# blinkercough.net
KiCad netlist of a schematic drawn in EAGLE
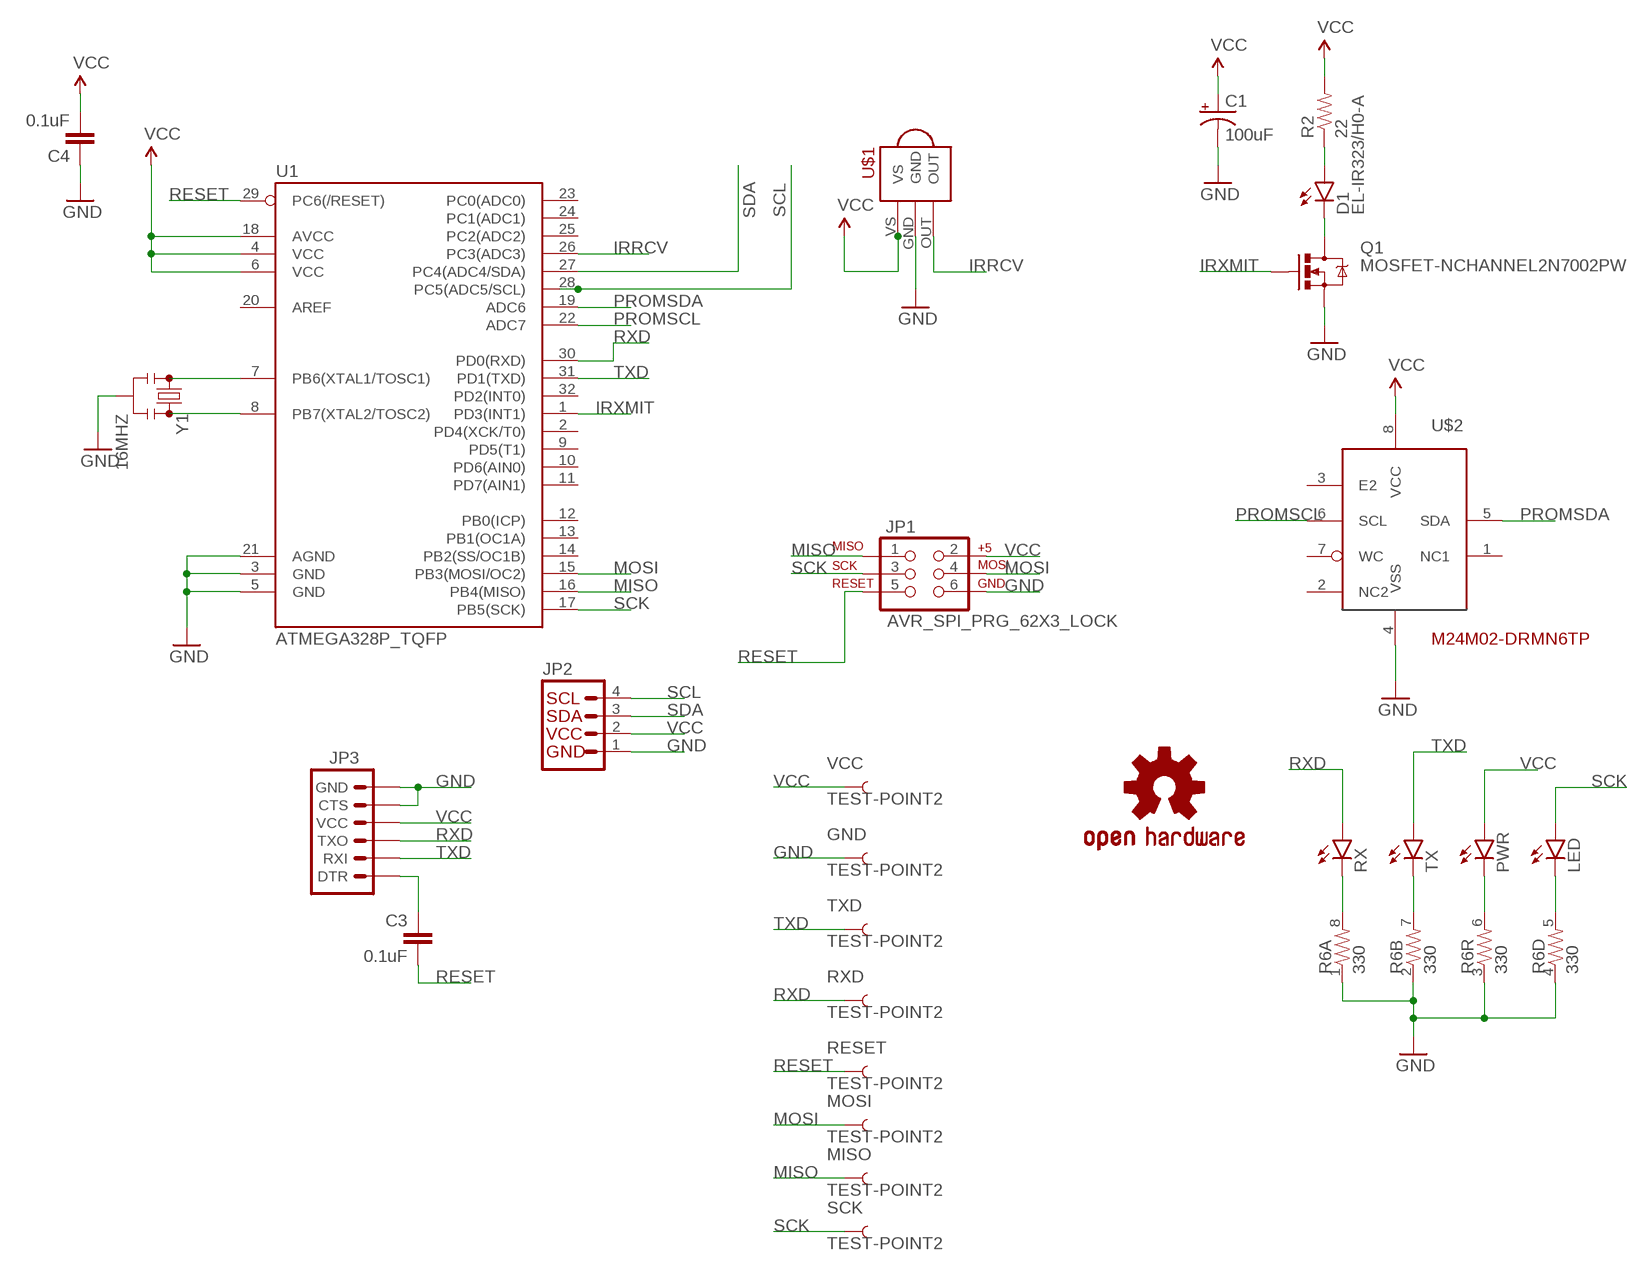
[diagram p0: schematic, sheet 1]

(export (version "E")
  (design (tool "Eeschema 10.0.6"))
  (components
    (comp (ref "C1")
      (value "100uF")
      (footprint "eagle-import:EIA7343")
      (libsource (lib "eagle-import") (part "100UF-10V-10%(TANT)"))
    )
    (comp (ref "C3")
      (value "0.1uF")
      (footprint "eagle-import:0603-CAP")
      (libsource (lib "eagle-import") (part "0.1UF-25V(+80/-20%)(0603)"))
    )
    (comp (ref "C4")
      (value "0.1uF")
      (footprint "eagle-import:0603-CAP")
      (libsource (lib "eagle-import") (part "0.1UF-25V(+80/-20%)(0603)"))
    )
    (comp (ref "D1")
      (value "EL-IR323/H0-A")
      (footprint "eagle-import:LED3MM")
      (libsource (lib "eagle-import") (part "LED3MM"))
    )
    (comp (ref "GND")
      (value "TEST-POINT2")
      (footprint "eagle-import:PAD.02X.02")
      (libsource (lib "eagle-import") (part "TEST-POINT2"))
    )
    (comp (ref "JP1")
      (value "AVR_SPI_PRG_62X3_LOCK")
      (footprint "eagle-import:2X3_LOCK")
      (libsource (lib "eagle-import") (part "AVR_SPI_PRG_62X3_LOCK"))
    )
    (comp (ref "JP2")
      (value "I2C_STANDARD")
      (footprint "eagle-import:1X04")
      (libsource (lib "eagle-import") (part "I2C_STANDARD"))
    )
    (comp (ref "JP3")
      (value "ARDUINO_SERIAL_PROGRAMLOCK")
      (footprint "eagle-import:1X06_LOCK")
      (libsource (lib "eagle-import") (part "ARDUINO_SERIAL_PROGRAMLOCK"))
    )
    (comp (ref "LED")
      (value "LED0603")
      (footprint "eagle-import:LED-0603")
      (libsource (lib "eagle-import") (part "LED0603"))
    )
    (comp (ref "LOGO1")
      (value "OSHW-LOGOS")
      (footprint "eagle-import:OSHW-LOGO-S")
      (libsource (lib "eagle-import") (part "OSHW-LOGOS"))
    )
    (comp (ref "MISO")
      (value "TEST-POINT2")
      (footprint "eagle-import:PAD.02X.02")
      (libsource (lib "eagle-import") (part "TEST-POINT2"))
    )
    (comp (ref "MOSI")
      (value "TEST-POINT2")
      (footprint "eagle-import:PAD.02X.02")
      (libsource (lib "eagle-import") (part "TEST-POINT2"))
    )
    (comp (ref "PWR")
      (value "LED0603")
      (footprint "eagle-import:LED-0603")
      (libsource (lib "eagle-import") (part "LED0603"))
    )
    (comp (ref "Q1")
      (value "MOSFET-NCHANNEL2N7002PW")
      (footprint "eagle-import:SOT323")
      (libsource (lib "eagle-import") (part "MOSFET-NCHANNEL2N7002PW"))
    )
    (comp (ref "R2")
      (value "22")
      (footprint "eagle-import:1206")
      (libsource (lib "eagle-import") (part "RESISTOR1206"))
    )
    (comp (ref "R6")
      (value "330")
      (footprint "eagle-import:0603-ARV")
      (libsource (lib "eagle-import") (part "RESISTOR-ARRAY0603-ARV"))
    )
    (comp (ref "RESET")
      (value "TEST-POINT2")
      (footprint "eagle-import:PAD.02X.02")
      (libsource (lib "eagle-import") (part "TEST-POINT2"))
    )
    (comp (ref "RX")
      (value "LED0603")
      (footprint "eagle-import:LED-0603")
      (libsource (lib "eagle-import") (part "LED0603"))
    )
    (comp (ref "RXD")
      (value "TEST-POINT2")
      (footprint "eagle-import:PAD.02X.02")
      (libsource (lib "eagle-import") (part "TEST-POINT2"))
    )
    (comp (ref "SCK")
      (value "TEST-POINT2")
      (footprint "eagle-import:PAD.02X.02")
      (libsource (lib "eagle-import") (part "TEST-POINT2"))
    )
    (comp (ref "TX")
      (value "LED0603")
      (footprint "eagle-import:LED-0603")
      (libsource (lib "eagle-import") (part "LED0603"))
    )
    (comp (ref "TXD")
      (value "TEST-POINT2")
      (footprint "eagle-import:PAD.02X.02")
      (libsource (lib "eagle-import") (part "TEST-POINT2"))
    )
    (comp (ref "U$1")
      (value "TSOP2438")
      (footprint "eagle-import:TSOP2438")
      (libsource (lib "eagle-import") (part "TSOP2438"))
    )
    (comp (ref "U$2")
      (value "M24M02-DRMN6TP")
      (footprint "eagle-import:SO8")
      (libsource (lib "eagle-import") (part "M24M02-DRMN6TP"))
    )
    (comp (ref "U1")
      (value "ATMEGA328P_TQFP")
      (footprint "eagle-import:TQFP32-08")
      (libsource (lib "eagle-import") (part "ATMEGA328P_TQFP"))
    )
    (comp (ref "VCC")
      (value "TEST-POINT2")
      (footprint "eagle-import:PAD.02X.02")
      (libsource (lib "eagle-import") (part "TEST-POINT2"))
    )
    (comp (ref "Y1")
      (value "16MHZ")
      (footprint "eagle-import:RESONATOR-SMD")
      (libsource (lib "eagle-import") (part "RESONATOR16MHZ"))
    )
  )
  (nets
    (net (code "1") (name "/IRRCV") (class "Default")
      (node (ref "U$1") (pin "OUT") (pinfunction "OUT_OUT") (pintype "output"))
      (node (ref "U1") (pin "26") (pinfunction "PC3(ADC3)_26") (pintype "bidirectional"))
    )
    (net (code "2") (name "/IRXMIT") (class "Default")
      (node (ref "Q1") (pin "1") (pinfunction "G_1") (pintype "passive"))
      (node (ref "U1") (pin "1") (pinfunction "PD3(INT1)_1") (pintype "bidirectional"))
    )
    (net (code "3") (name "/MISO") (class "Default")
      (node (ref "JP1") (pin "1") (pinfunction "1_1") (pintype "passive"))
      (node (ref "MISO") (pin "P$1") (pinfunction "1_P$1") (pintype "bidirectional"))
      (node (ref "U1") (pin "16") (pinfunction "PB4(MISO)_16") (pintype "bidirectional"))
    )
    (net (code "4") (name "/MOSI") (class "Default")
      (node (ref "JP1") (pin "4") (pinfunction "4_4") (pintype "passive"))
      (node (ref "MOSI") (pin "P$1") (pinfunction "1_P$1") (pintype "bidirectional"))
      (node (ref "U1") (pin "15") (pinfunction "PB3(MOSI/OC2)_15") (pintype "bidirectional"))
    )
    (net (code "5") (name "/PROMSCL") (class "Default")
      (node (ref "U$2") (pin "6") (pinfunction "SCL_6") (pintype "bidirectional"))
      (node (ref "U1") (pin "22") (pinfunction "ADC7_22") (pintype "bidirectional"))
    )
    (net (code "6") (name "/PROMSDA") (class "Default")
      (node (ref "U$2") (pin "5") (pinfunction "SDA_5") (pintype "bidirectional"))
      (node (ref "U1") (pin "19") (pinfunction "ADC6_19") (pintype "bidirectional"))
    )
    (net (code "7") (name "/RESET") (class "Default")
      (node (ref "C3") (pin "2") (pinfunction "2_2") (pintype "passive"))
      (node (ref "JP1") (pin "5") (pinfunction "5_5") (pintype "passive"))
      (node (ref "RESET") (pin "P$1") (pinfunction "1_P$1") (pintype "bidirectional"))
      (node (ref "U1") (pin "29") (pinfunction "PC6(/RESET)_29") (pintype "bidirectional"))
    )
    (net (code "8") (name "/RXD") (class "Default")
      (node (ref "JP3") (pin "3") (pinfunction "TXO_3") (pintype "passive"))
      (node (ref "RX") (pin "A") (pinfunction "A_A") (pintype "passive"))
      (node (ref "RXD") (pin "P$1") (pinfunction "1_P$1") (pintype "bidirectional"))
      (node (ref "U1") (pin "30") (pinfunction "PD0(RXD)_30") (pintype "bidirectional"))
    )
    (net (code "9") (name "/SCK") (class "Default")
      (node (ref "JP1") (pin "3") (pinfunction "3_3") (pintype "passive"))
      (node (ref "LED") (pin "A") (pinfunction "A_A") (pintype "passive"))
      (node (ref "SCK") (pin "P$1") (pinfunction "1_P$1") (pintype "bidirectional"))
      (node (ref "U1") (pin "17") (pinfunction "PB5(SCK)_17") (pintype "bidirectional"))
    )
    (net (code "10") (name "/SCL") (class "Default")
      (node (ref "JP2") (pin "4") (pinfunction "4_4") (pintype "passive"))
      (node (ref "U1") (pin "28") (pinfunction "PC5(ADC5/SCL)_28") (pintype "bidirectional"))
    )
    (net (code "11") (name "/SDA") (class "Default")
      (node (ref "JP2") (pin "3") (pinfunction "3_3") (pintype "passive"))
      (node (ref "U1") (pin "27") (pinfunction "PC4(ADC4/SDA)_27") (pintype "bidirectional"))
    )
    (net (code "12") (name "/TXD") (class "Default")
      (node (ref "JP3") (pin "2") (pinfunction "RXI_2") (pintype "passive"))
      (node (ref "TX") (pin "A") (pinfunction "A_A") (pintype "passive"))
      (node (ref "TXD") (pin "P$1") (pinfunction "1_P$1") (pintype "bidirectional"))
      (node (ref "U1") (pin "31") (pinfunction "PD1(TXD)_31") (pintype "bidirectional"))
    )
    (net (code "13") (name "GND") (class "Default")
      (node (ref "C1") (pin "C") (pinfunction "-_C") (pintype "passive"))
      (node (ref "C4") (pin "1") (pinfunction "1_1") (pintype "passive"))
      (node (ref "GND") (pin "P$1") (pinfunction "1_P$1") (pintype "bidirectional"))
      (node (ref "JP1") (pin "6") (pinfunction "6_6") (pintype "passive"))
      (node (ref "JP2") (pin "1") (pinfunction "1_1") (pintype "passive"))
      (node (ref "JP3") (pin "5") (pinfunction "CTS_5") (pintype "passive"))
      (node (ref "JP3") (pin "6") (pinfunction "GND_6") (pintype "passive"))
      (node (ref "Q1") (pin "2") (pinfunction "S_2") (pintype "passive"))
      (node (ref "R6") (pin "1") (pinfunction "1_1") (pintype "passive"))
      (node (ref "R6") (pin "2") (pinfunction "1_2") (pintype "passive"))
      (node (ref "R6") (pin "3") (pinfunction "1_3") (pintype "passive"))
      (node (ref "R6") (pin "4") (pinfunction "1_4") (pintype "passive"))
      (node (ref "U$1") (pin "GND") (pinfunction "GND_GND") (pintype "power_in"))
      (node (ref "U$2") (pin "4") (pinfunction "VSS_4") (pintype "bidirectional"))
      (node (ref "U1") (pin "21") (pinfunction "AGND_21") (pintype "bidirectional"))
      (node (ref "U1") (pin "3") (pinfunction "GND_3") (pintype "bidirectional"))
      (node (ref "U1") (pin "5") (pinfunction "GND_5") (pintype "bidirectional"))
      (node (ref "Y1") (pin "2") (pinfunction "2_2") (pintype "passive"))
    )
    (net (code "14") (name "Net-(D1-C)") (class "Default")
      (node (ref "D1") (pin "K") (pinfunction "C_K") (pintype "passive"))
      (node (ref "Q1") (pin "3") (pinfunction "D_3") (pintype "passive"))
    )
    (net (code "15") (name "Net-(D1-PadA)") (class "Default")
      (node (ref "D1") (pin "A") (pinfunction "A_A") (pintype "passive"))
      (node (ref "R2") (pin "1") (pinfunction "1_1") (pintype "passive"))
    )
    (net (code "16") (name "Net-(JP3-DTR)") (class "Default")
      (node (ref "C3") (pin "1") (pinfunction "1_1") (pintype "passive"))
      (node (ref "JP3") (pin "1") (pinfunction "DTR_1") (pintype "passive"))
    )
    (net (code "17") (name "Net-(R6A-2)") (class "Default")
      (node (ref "R6") (pin "8") (pinfunction "2_8") (pintype "passive"))
      (node (ref "RX") (pin "C") (pinfunction "C_C") (pintype "passive"))
    )
    (net (code "18") (name "Net-(R6B-2)") (class "Default")
      (node (ref "R6") (pin "7") (pinfunction "2_7") (pintype "passive"))
      (node (ref "TX") (pin "C") (pinfunction "C_C") (pintype "passive"))
    )
    (net (code "19") (name "Net-(R6C-2)") (class "Default")
      (node (ref "LED") (pin "C") (pinfunction "C_C") (pintype "passive"))
      (node (ref "R6") (pin "5") (pinfunction "2_5") (pintype "passive"))
    )
    (net (code "20") (name "Net-(R6D-2)") (class "Default")
      (node (ref "PWR") (pin "C") (pinfunction "C_C") (pintype "passive"))
      (node (ref "R6") (pin "6") (pinfunction "2_6") (pintype "passive"))
    )
    (net (code "21") (name "Net-(U1-PB6(XTAL1{slash}TOSC1))") (class "Default")
      (node (ref "U1") (pin "7") (pinfunction "PB6(XTAL1/TOSC1)_7") (pintype "bidirectional"))
      (node (ref "Y1") (pin "1") (pinfunction "1_1") (pintype "passive"))
    )
    (net (code "22") (name "Net-(U1-PB7(XTAL2{slash}TOSC2))") (class "Default")
      (node (ref "U1") (pin "8") (pinfunction "PB7(XTAL2/TOSC2)_8") (pintype "bidirectional"))
      (node (ref "Y1") (pin "3") (pinfunction "3_3") (pintype "passive"))
    )
    (net (code "23") (name "VCC") (class "Default")
      (node (ref "C1") (pin "A") (pinfunction "+_A") (pintype "passive"))
      (node (ref "C4") (pin "2") (pinfunction "2_2") (pintype "passive"))
      (node (ref "JP1") (pin "2") (pinfunction "2_2") (pintype "passive"))
      (node (ref "JP2") (pin "2") (pinfunction "2_2") (pintype "passive"))
      (node (ref "JP3") (pin "4") (pinfunction "VCC_4") (pintype "passive"))
      (node (ref "PWR") (pin "A") (pinfunction "A_A") (pintype "passive"))
      (node (ref "R2") (pin "2") (pinfunction "2_2") (pintype "passive"))
      (node (ref "U$1") (pin "VS") (pinfunction "VS_VS") (pintype "power_in"))
      (node (ref "U$2") (pin "8") (pinfunction "VCC_8") (pintype "bidirectional"))
      (node (ref "U1") (pin "18") (pinfunction "AVCC_18") (pintype "bidirectional"))
      (node (ref "U1") (pin "4") (pinfunction "VCC_4") (pintype "bidirectional"))
      (node (ref "U1") (pin "6") (pinfunction "VCC_6") (pintype "bidirectional"))
      (node (ref "VCC") (pin "P$1") (pinfunction "1_P$1") (pintype "bidirectional"))
    )
    (net (code "24") (name "unconnected-(U$2-E2-Pad3)") (class "Default")
      (node (ref "U$2") (pin "3") (pinfunction "E2_3") (pintype "input"))
    )
    (net (code "25") (name "unconnected-(U$2-NC1-Pad1)") (class "Default")
      (node (ref "U$2") (pin "1") (pinfunction "NC1_1") (pintype "no_connect"))
    )
    (net (code "26") (name "unconnected-(U$2-NC2-Pad2)") (class "Default")
      (node (ref "U$2") (pin "2") (pinfunction "NC2_2") (pintype "no_connect"))
    )
    (net (code "27") (name "unconnected-(U$2-WC-Pad7)") (class "Default")
      (node (ref "U$2") (pin "7") (pinfunction "WC_7") (pintype "input"))
    )
    (net (code "28") (name "unconnected-(U1-AREF-Pad20)") (class "Default")
      (node (ref "U1") (pin "20") (pinfunction "AREF_20") (pintype "bidirectional"))
    )
    (net (code "29") (name "unconnected-(U1-PB0(ICP)-Pad12)") (class "Default")
      (node (ref "U1") (pin "12") (pinfunction "PB0(ICP)_12") (pintype "bidirectional"))
    )
    (net (code "30") (name "unconnected-(U1-PB1(OC1A)-Pad13)") (class "Default")
      (node (ref "U1") (pin "13") (pinfunction "PB1(OC1A)_13") (pintype "bidirectional"))
    )
    (net (code "31") (name "unconnected-(U1-PB2(SS{slash}OC1B)-Pad14)") (class "Default")
      (node (ref "U1") (pin "14") (pinfunction "PB2(SS/OC1B)_14") (pintype "bidirectional"))
    )
    (net (code "32") (name "unconnected-(U1-PC0(ADC0)-Pad23)") (class "Default")
      (node (ref "U1") (pin "23") (pinfunction "PC0(ADC0)_23") (pintype "bidirectional"))
    )
    (net (code "33") (name "unconnected-(U1-PC1(ADC1)-Pad24)") (class "Default")
      (node (ref "U1") (pin "24") (pinfunction "PC1(ADC1)_24") (pintype "bidirectional"))
    )
    (net (code "34") (name "unconnected-(U1-PC2(ADC2)-Pad25)") (class "Default")
      (node (ref "U1") (pin "25") (pinfunction "PC2(ADC2)_25") (pintype "bidirectional"))
    )
    (net (code "35") (name "unconnected-(U1-PD2(INT0)-Pad32)") (class "Default")
      (node (ref "U1") (pin "32") (pinfunction "PD2(INT0)_32") (pintype "bidirectional"))
    )
    (net (code "36") (name "unconnected-(U1-PD4(XCK{slash}T0)-Pad2)") (class "Default")
      (node (ref "U1") (pin "2") (pinfunction "PD4(XCK/T0)_2") (pintype "bidirectional"))
    )
    (net (code "37") (name "unconnected-(U1-PD5(T1)-Pad9)") (class "Default")
      (node (ref "U1") (pin "9") (pinfunction "PD5(T1)_9") (pintype "bidirectional"))
    )
    (net (code "38") (name "unconnected-(U1-PD6(AIN0)-Pad10)") (class "Default")
      (node (ref "U1") (pin "10") (pinfunction "PD6(AIN0)_10") (pintype "bidirectional"))
    )
    (net (code "39") (name "unconnected-(U1-PD7(AIN1)-Pad11)") (class "Default")
      (node (ref "U1") (pin "11") (pinfunction "PD7(AIN1)_11") (pintype "bidirectional"))
    )
  )
)
